# ADC_Subsystem.net
KiCad netlist of a schematic drawn in Altium Designer
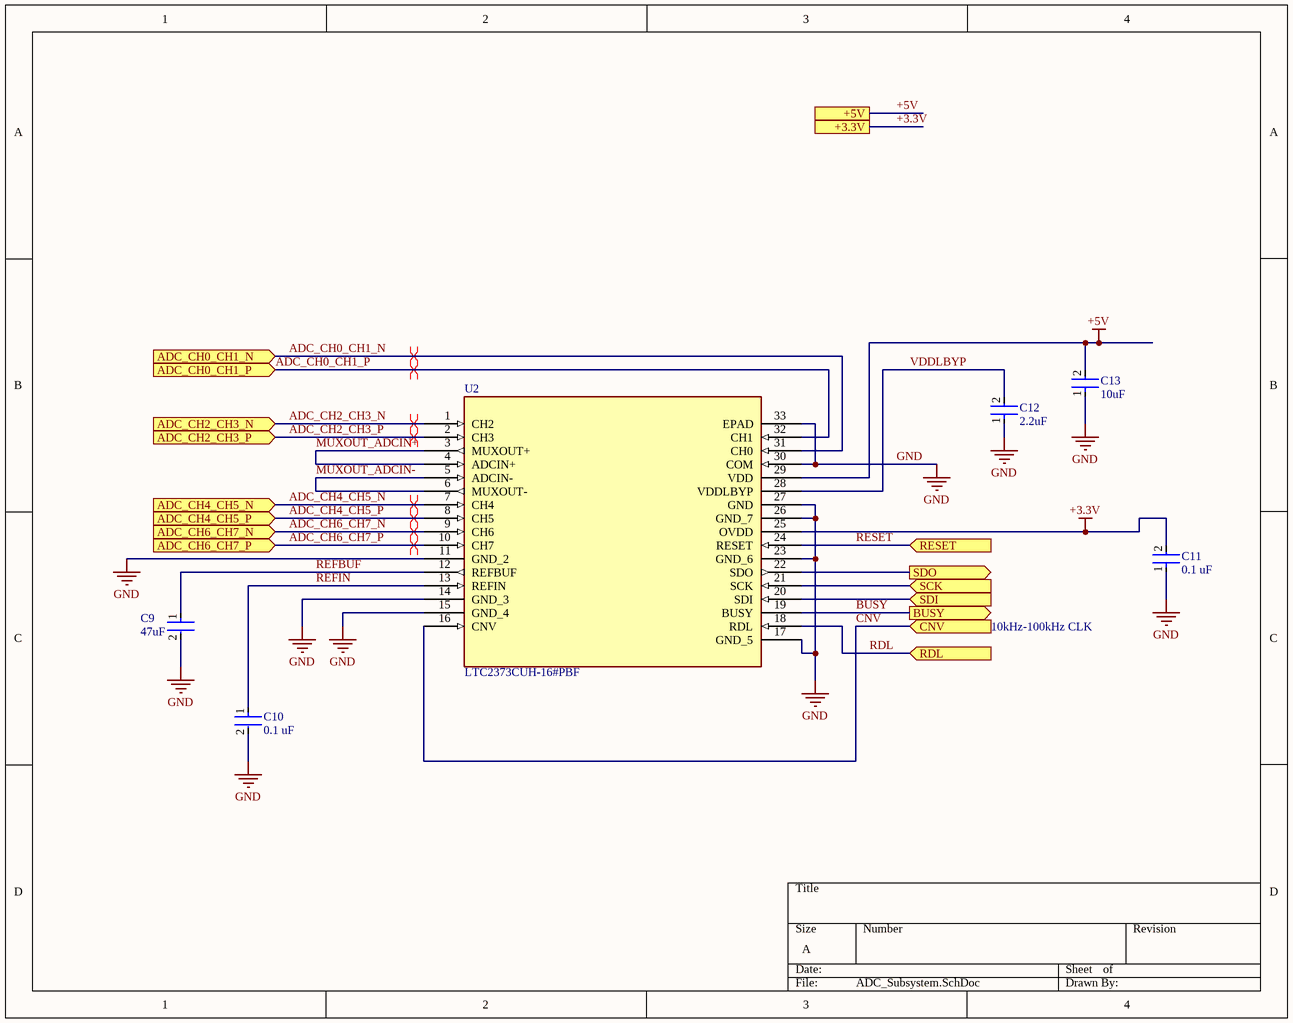
[diagram p0: ADC_Subsystem.SchDoc]

(export (version "E")
  (design (tool "Eeschema 10.0.6"))
  (components
    (comp (ref "C9")
      (value "47uF")
      (footprint "FP-C0805C476M9PACTU-MFG")
      (description "CAP CER 47UF 6.3V X5R 0805\r\nC0805C476M9PACTU")
      (fields (field (name "VOLTAGE") "6.3V") (field (name "TOLERANCE") "20%"))
      (libsource (lib "Altium Content Vault") (part "11868f565c42a9108669ba33697ecf6"))
    )
    (comp (ref "C10")
      (value "0.1 uF")
      (footprint "FP-CC0603-DA-MFG")
      (description "CAP CER 0.1UF 16V X7R 0603 CC0603KRX7R7BB104")
      (fields
        (field (name "OCTOPART") "https://octopart.com/cc0603krx7r7bb104-yageo-192941")
        (field (name "TOLERANCE") "0.1")
      )
      (libsource (lib "Altium Content Vault") (part "11868f565c42a9108669ba33697ecf6"))
    )
    (comp (ref "C11")
      (value "0.1 uF")
      (footprint "FP-CC0603-DA-MFG")
      (description "CAP CER 0.1UF 16V X7R 0603 CC0603KRX7R7BB104")
      (fields
        (field (name "OCTOPART") "https://octopart.com/cc0603krx7r7bb104-yageo-192941")
        (field (name "TOLERANCE") "0.1")
      )
      (libsource (lib "Altium Content Vault") (part "11868f565c42a9108669ba33697ecf6"))
    )
    (comp (ref "C12")
      (value "2.2uF")
      (footprint "FP-GRM188-0_1-e0_2_0_5-MFG")
      (fields (field (name "VOLTAGE") "10V") (field (name "TOLERANCE") "10%"))
      (libsource (lib "Altium Content Vault") (part "11868f565c42a9108669ba33697ecf6"))
    )
    (comp (ref "C13")
      (value "10uF")
      (footprint "FP-GRM188-0_1-e0_2_0_55-IPC_A")
      (fields (field (name "VOLTAGE") "6.3V") (field (name "TOLERANCE") "20%"))
      (libsource (lib "Altium Content Vault") (part "02cd4be3c70576c341d710602a673aa"))
    )
    (comp (ref "U2")
      (value "LTC2373CUH-16#PBF")
      (footprint "LTC_2373_Footprint")
      (libsource (lib "LTC2373CUH-16#PBF") (part "LTC2373CUH-16#PBF"))
    )
  )
  (nets
    (net (code "1") (name "+3.3V") (class "Default")
      (node (ref "C11") (pin "2") (pinfunction "2_2") (pintype "passive"))
      (node (ref "U2") (pin "25") (pinfunction "OVDD_25") (pintype "power_in"))
    )
    (net (code "2") (name "+5V") (class "Default")
      (node (ref "C13") (pin "2") (pinfunction "2_2") (pintype "passive"))
      (node (ref "U2") (pin "29") (pinfunction "VDD_29") (pintype "power_in"))
    )
    (net (code "3") (name "/ADC_CH0_CH1_N") (class "Default")
      (node (ref "U2") (pin "31") (pinfunction "CH0_31") (pintype "input"))
    )
    (net (code "4") (name "/ADC_CH0_CH1_P") (class "Default")
      (node (ref "U2") (pin "32") (pinfunction "CH1_32") (pintype "input"))
    )
    (net (code "5") (name "/ADC_CH2_CH3_N") (class "Default")
      (node (ref "U2") (pin "1") (pinfunction "CH2_1") (pintype "input"))
    )
    (net (code "6") (name "/ADC_CH2_CH3_P") (class "Default")
      (node (ref "U2") (pin "2") (pinfunction "CH3_2") (pintype "input"))
    )
    (net (code "7") (name "/ADC_CH4_CH5_N") (class "Default")
      (node (ref "U2") (pin "7") (pinfunction "CH4_7") (pintype "input"))
    )
    (net (code "8") (name "/ADC_CH4_CH5_P") (class "Default")
      (node (ref "U2") (pin "8") (pinfunction "CH5_8") (pintype "input"))
    )
    (net (code "9") (name "/ADC_CH6_CH7_N") (class "Default")
      (node (ref "U2") (pin "9") (pinfunction "CH6_9") (pintype "input"))
    )
    (net (code "10") (name "/ADC_CH6_CH7_P") (class "Default")
      (node (ref "U2") (pin "10") (pinfunction "CH7_10") (pintype "input"))
    )
    (net (code "11") (name "/BUSY") (class "Default")
      (node (ref "U2") (pin "19") (pinfunction "BUSY_19") (pintype "passive"))
    )
    (net (code "12") (name "/CNV") (class "Default")
      (node (ref "U2") (pin "16") (pinfunction "CNV_16") (pintype "input"))
    )
    (net (code "13") (name "/MUXOUT_ADCIN+") (class "Default")
      (node (ref "U2") (pin "3") (pinfunction "MUXOUT+_3") (pintype "output"))
      (node (ref "U2") (pin "4") (pinfunction "ADCIN+_4") (pintype "input"))
    )
    (net (code "14") (name "/MUXOUT_ADCIN-") (class "Default")
      (node (ref "U2") (pin "5") (pinfunction "ADCIN-_5") (pintype "input"))
      (node (ref "U2") (pin "6") (pinfunction "MUXOUT-_6") (pintype "output"))
    )
    (net (code "15") (name "/RDL") (class "Default")
      (node (ref "U2") (pin "18") (pinfunction "RDL_18") (pintype "input"))
    )
    (net (code "16") (name "/REFBUF") (class "Default")
      (node (ref "C9") (pin "1") (pinfunction "1_1") (pintype "passive"))
      (node (ref "U2") (pin "12") (pinfunction "REFBUF_12") (pintype "output"))
    )
    (net (code "17") (name "/REFIN") (class "Default")
      (node (ref "C10") (pin "1") (pinfunction "1_1") (pintype "passive"))
      (node (ref "U2") (pin "13") (pinfunction "REFIN_13") (pintype "input"))
    )
    (net (code "18") (name "/RESET") (class "Default")
      (node (ref "U2") (pin "24") (pinfunction "RESET_24") (pintype "input"))
    )
    (net (code "19") (name "/SCK") (class "Default")
      (node (ref "U2") (pin "21") (pinfunction "SCK_21") (pintype "input"))
    )
    (net (code "20") (name "/SDI") (class "Default")
      (node (ref "U2") (pin "20") (pinfunction "SDI_20") (pintype "input"))
    )
    (net (code "21") (name "/SDO") (class "Default")
      (node (ref "U2") (pin "22") (pinfunction "SDO_22") (pintype "output"))
    )
    (net (code "22") (name "/VDDLBYP") (class "Default")
      (node (ref "C12") (pin "2") (pinfunction "2_2") (pintype "passive"))
      (node (ref "U2") (pin "28") (pinfunction "VDDLBYP_28") (pintype "power_in"))
    )
    (net (code "23") (name "GND") (class "Default")
      (node (ref "C10") (pin "2") (pinfunction "2_2") (pintype "passive"))
      (node (ref "C11") (pin "1") (pinfunction "1_1") (pintype "passive"))
      (node (ref "C12") (pin "1") (pinfunction "1_1") (pintype "passive"))
      (node (ref "C13") (pin "1") (pinfunction "1_1") (pintype "passive"))
      (node (ref "C9") (pin "2") (pinfunction "2_2") (pintype "passive"))
      (node (ref "U2") (pin "11") (pinfunction "GND_2_11") (pintype "power_in"))
      (node (ref "U2") (pin "14") (pinfunction "GND_3_14") (pintype "power_in"))
      (node (ref "U2") (pin "15") (pinfunction "GND_4_15") (pintype "power_in"))
      (node (ref "U2") (pin "17") (pinfunction "GND_5_17") (pintype "power_in"))
      (node (ref "U2") (pin "23") (pinfunction "GND_6_23") (pintype "power_in"))
      (node (ref "U2") (pin "26") (pinfunction "GND_7_26") (pintype "power_in"))
      (node (ref "U2") (pin "27") (pinfunction "GND_27") (pintype "power_in"))
      (node (ref "U2") (pin "30") (pinfunction "COM_30") (pintype "input"))
      (node (ref "U2") (pin "33") (pinfunction "EPAD_33") (pintype "passive"))
    )
  )
)
